# MK64_Power_ADC.net
KiCad netlist of a schematic drawn in Altium Designer
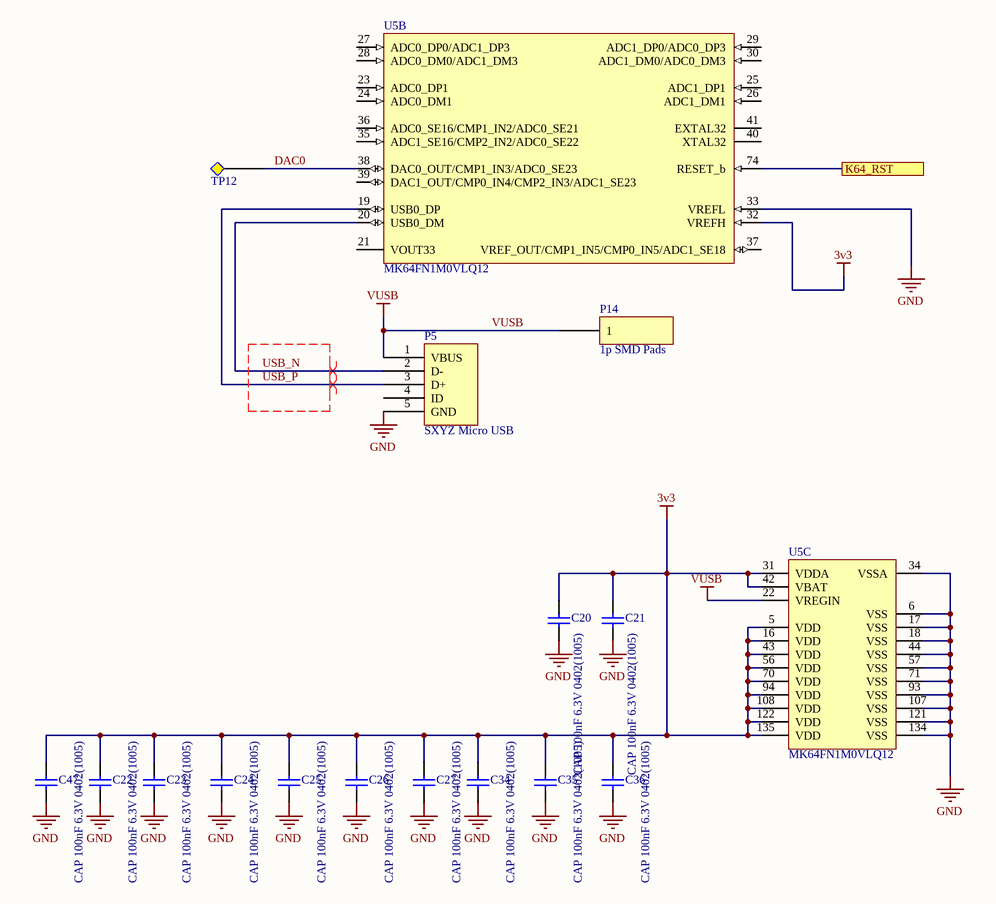
[diagram p0: MK64 Power ADC.SchDoc]

(export (version "E")
  (design (tool "Eeschema 10.0.6"))
  (components
    (comp (ref "C20")
      (value "CAP 100nF 6.3V 0402(1005)")
      (footprint "CAPC0402(1005)60_M")
      (description "CAP 100nF 6.3V ±20% 0402 (1005 Metric) Thickness 0.6mm SMD")
      (fields (field (name "TOLERANCE") "Â±20%"))
      (libsource (lib "Altium Content Vault") (part "CAP"))
    )
    (comp (ref "C21")
      (value "CAP 100nF 6.3V 0402(1005)")
      (footprint "CAPC0402(1005)60_M")
      (description "CAP 100nF 6.3V ±20% 0402 (1005 Metric) Thickness 0.6mm SMD")
      (fields (field (name "TOLERANCE") "Â±20%"))
      (libsource (lib "Altium Content Vault") (part "CAP"))
    )
    (comp (ref "C22")
      (value "CAP 100nF 6.3V 0402(1005)")
      (footprint "CAPC0402(1005)60_M")
      (description "CAP 100nF 6.3V ±20% 0402 (1005 Metric) Thickness 0.6mm SMD")
      (fields (field (name "TOLERANCE") "Â±20%"))
      (libsource (lib "Altium Content Vault") (part "CAP"))
    )
    (comp (ref "C23")
      (value "CAP 100nF 6.3V 0402(1005)")
      (footprint "CAPC0402(1005)60_M")
      (description "CAP 100nF 6.3V ±20% 0402 (1005 Metric) Thickness 0.6mm SMD")
      (fields (field (name "TOLERANCE") "Â±20%"))
      (libsource (lib "Altium Content Vault") (part "CAP"))
    )
    (comp (ref "C24")
      (value "CAP 100nF 6.3V 0402(1005)")
      (footprint "CAPC0402(1005)60_M")
      (description "CAP 100nF 6.3V ±20% 0402 (1005 Metric) Thickness 0.6mm SMD")
      (fields (field (name "TOLERANCE") "Â±20%"))
      (libsource (lib "Altium Content Vault") (part "CAP"))
    )
    (comp (ref "C25")
      (value "CAP 100nF 6.3V 0402(1005)")
      (footprint "CAPC0402(1005)60_M")
      (description "CAP 100nF 6.3V ±20% 0402 (1005 Metric) Thickness 0.6mm SMD")
      (fields (field (name "TOLERANCE") "Â±20%"))
      (libsource (lib "Altium Content Vault") (part "CAP"))
    )
    (comp (ref "C26")
      (value "CAP 100nF 6.3V 0402(1005)")
      (footprint "CAPC0402(1005)60_M")
      (description "CAP 100nF 6.3V ±20% 0402 (1005 Metric) Thickness 0.6mm SMD")
      (fields (field (name "TOLERANCE") "Â±20%"))
      (libsource (lib "Altium Content Vault") (part "CAP"))
    )
    (comp (ref "C27")
      (value "CAP 100nF 6.3V 0402(1005)")
      (footprint "CAPC0402(1005)60_M")
      (description "CAP 100nF 6.3V ±20% 0402 (1005 Metric) Thickness 0.6mm SMD")
      (fields (field (name "TOLERANCE") "Â±20%"))
      (libsource (lib "Altium Content Vault") (part "CAP"))
    )
    (comp (ref "C34")
      (value "CAP 100nF 6.3V 0402(1005)")
      (footprint "CAPC0402(1005)60_M")
      (description "CAP 100nF 6.3V ±20% 0402 (1005 Metric) Thickness 0.6mm SMD")
      (fields (field (name "TOLERANCE") "Â±20%"))
      (libsource (lib "Altium Content Vault") (part "CAP"))
    )
    (comp (ref "C35")
      (value "CAP 100nF 6.3V 0402(1005)")
      (footprint "CAPC0402(1005)60_M")
      (description "CAP 100nF 6.3V ±20% 0402 (1005 Metric) Thickness 0.6mm SMD")
      (fields (field (name "TOLERANCE") "Â±20%"))
      (libsource (lib "Altium Content Vault") (part "CAP"))
    )
    (comp (ref "C36")
      (value "CAP 100nF 6.3V 0402(1005)")
      (footprint "CAPC0402(1005)60_M")
      (description "CAP 100nF 6.3V ±20% 0402 (1005 Metric) Thickness 0.6mm SMD")
      (fields (field (name "TOLERANCE") "Â±20%"))
      (libsource (lib "Altium Content Vault") (part "CAP"))
    )
    (comp (ref "C47")
      (value "CAP 100nF 6.3V 0402(1005)")
      (footprint "CAPC0402(1005)60_M")
      (description "CAP 100nF 6.3V ±20% 0402 (1005 Metric) Thickness 0.6mm SMD")
      (fields (field (name "TOLERANCE") "Â±20%"))
      (libsource (lib "Altium Content Vault") (part "CAP"))
    )
    (comp (ref "P5")
      (value "SXYZ Micro USB")
      (footprint "SXYZ Micro USB")
      (description "Micro USB Connector")
      (libsource (lib "parts") (part "SXYZ MicroUSB"))
    )
    (comp (ref "P14")
      (value "1p SMD Pads")
      (footprint "1p SMD pad")
      (libsource (lib "parts") (part "1p SMD"))
    )
    (comp (ref "TP12") (value "Test Point") (footprint "TP") (libsource (lib "parts") (part "TP")))
    (comp (ref "U5")
      (value "MK64FN1M0VLQ12")
      (footprint "918-03_N")
      (fields (field (name "MANUFACTURER") "Freescale Semiconductor"))
      (libsource (lib "Altium Content Vault") (part "FRES-MK64FX512VLQ12-144"))
    )
  )
  (nets
    (net (code "1") (name "/DAC0") (class "Default")
      (node (ref "TP12") (pin "1") (pinfunction "1_1") (pintype "passive"))
      (node (ref "U5") (pin "38") (pinfunction "DAC0_OUT/CMP1_IN3/ADC0_SE23_38") (pintype "bidirectional"))
    )
    (net (code "2") (name "/K64_RST") (class "Default")
      (node (ref "U5") (pin "74") (pinfunction "RESET_b_74") (pintype "input"))
    )
    (net (code "3") (name "/USB_N") (class "Default")
      (node (ref "P5") (pin "2") (pinfunction "D-_2") (pintype "passive"))
      (node (ref "U5") (pin "20") (pinfunction "USB0_DM_20") (pintype "bidirectional"))
    )
    (net (code "4") (name "/USB_P") (class "Default")
      (node (ref "P5") (pin "3") (pinfunction "D+_3") (pintype "passive"))
      (node (ref "U5") (pin "19") (pinfunction "USB0_DP_19") (pintype "bidirectional"))
    )
    (net (code "5") (name "3v3") (class "Default")
      (node (ref "C20") (pin "2") (pinfunction "2_2") (pintype "passive"))
      (node (ref "C21") (pin "2") (pinfunction "2_2") (pintype "passive"))
      (node (ref "C22") (pin "2") (pinfunction "2_2") (pintype "passive"))
      (node (ref "C23") (pin "2") (pinfunction "2_2") (pintype "passive"))
      (node (ref "C24") (pin "2") (pinfunction "2_2") (pintype "passive"))
      (node (ref "C25") (pin "2") (pinfunction "2_2") (pintype "passive"))
      (node (ref "C26") (pin "2") (pinfunction "2_2") (pintype "passive"))
      (node (ref "C27") (pin "2") (pinfunction "2_2") (pintype "passive"))
      (node (ref "C34") (pin "2") (pinfunction "2_2") (pintype "passive"))
      (node (ref "C35") (pin "2") (pinfunction "2_2") (pintype "passive"))
      (node (ref "C36") (pin "2") (pinfunction "2_2") (pintype "passive"))
      (node (ref "C47") (pin "2") (pinfunction "2_2") (pintype "passive"))
      (node (ref "U5") (pin "108") (pinfunction "VDD_108") (pintype "power_in"))
      (node (ref "U5") (pin "122") (pinfunction "VDD_122") (pintype "power_in"))
      (node (ref "U5") (pin "135") (pinfunction "VDD_135") (pintype "power_in"))
      (node (ref "U5") (pin "16") (pinfunction "VDD_16") (pintype "power_in"))
      (node (ref "U5") (pin "31") (pinfunction "VDDA_31") (pintype "power_in"))
      (node (ref "U5") (pin "32") (pinfunction "VREFH_32") (pintype "input"))
      (node (ref "U5") (pin "42") (pinfunction "VBAT_42") (pintype "power_in"))
      (node (ref "U5") (pin "43") (pinfunction "VDD_43") (pintype "power_in"))
      (node (ref "U5") (pin "5") (pinfunction "VDD_5") (pintype "power_in"))
      (node (ref "U5") (pin "56") (pinfunction "VDD_56") (pintype "power_in"))
      (node (ref "U5") (pin "70") (pinfunction "VDD_70") (pintype "power_in"))
      (node (ref "U5") (pin "94") (pinfunction "VDD_94") (pintype "power_in"))
    )
    (net (code "6") (name "GND") (class "Default")
      (node (ref "C20") (pin "1") (pinfunction "1_1") (pintype "passive"))
      (node (ref "C21") (pin "1") (pinfunction "1_1") (pintype "passive"))
      (node (ref "C22") (pin "1") (pinfunction "1_1") (pintype "passive"))
      (node (ref "C23") (pin "1") (pinfunction "1_1") (pintype "passive"))
      (node (ref "C24") (pin "1") (pinfunction "1_1") (pintype "passive"))
      (node (ref "C25") (pin "1") (pinfunction "1_1") (pintype "passive"))
      (node (ref "C26") (pin "1") (pinfunction "1_1") (pintype "passive"))
      (node (ref "C27") (pin "1") (pinfunction "1_1") (pintype "passive"))
      (node (ref "C34") (pin "1") (pinfunction "1_1") (pintype "passive"))
      (node (ref "C35") (pin "1") (pinfunction "1_1") (pintype "passive"))
      (node (ref "C36") (pin "1") (pinfunction "1_1") (pintype "passive"))
      (node (ref "C47") (pin "1") (pinfunction "1_1") (pintype "passive"))
      (node (ref "P5") (pin "5") (pinfunction "GND_5") (pintype "passive"))
      (node (ref "U5") (pin "107") (pinfunction "VSS_107") (pintype "power_in"))
      (node (ref "U5") (pin "121") (pinfunction "VSS_121") (pintype "power_in"))
      (node (ref "U5") (pin "134") (pinfunction "VSS_134") (pintype "power_in"))
      (node (ref "U5") (pin "17") (pinfunction "VSS_17") (pintype "power_in"))
      (node (ref "U5") (pin "18") (pinfunction "VSS_18") (pintype "power_in"))
      (node (ref "U5") (pin "33") (pinfunction "VREFL_33") (pintype "input"))
      (node (ref "U5") (pin "34") (pinfunction "VSSA_34") (pintype "power_in"))
      (node (ref "U5") (pin "44") (pinfunction "VSS_44") (pintype "power_in"))
      (node (ref "U5") (pin "57") (pinfunction "VSS_57") (pintype "power_in"))
      (node (ref "U5") (pin "6") (pinfunction "VSS_6") (pintype "power_in"))
      (node (ref "U5") (pin "71") (pinfunction "VSS_71") (pintype "power_in"))
      (node (ref "U5") (pin "93") (pinfunction "VSS_93") (pintype "power_in"))
    )
    (net (code "7") (name "VUSB") (class "Default")
      (node (ref "P14") (pin "1") (pinfunction "1_1") (pintype "passive"))
      (node (ref "P5") (pin "1") (pinfunction "VBUS_1") (pintype "passive"))
      (node (ref "U5") (pin "22") (pinfunction "VREGIN_22") (pintype "power_in"))
    )
    (net (code "8") (name "unconnected-(P5-ID-Pad4)") (class "Default")
      (node (ref "P5") (pin "4") (pinfunction "ID_4") (pintype "passive"))
    )
    (net (code "9") (name "unconnected-(U5B-ADC0_DM0{slash}ADC1_DM3-Pad28)") (class "Default")
      (node (ref "U5") (pin "28") (pinfunction "ADC0_DM0/ADC1_DM3_28") (pintype "input"))
    )
    (net (code "10") (name "unconnected-(U5B-ADC0_DM1-Pad24)") (class "Default")
      (node (ref "U5") (pin "24") (pinfunction "ADC0_DM1_24") (pintype "input"))
    )
    (net (code "11") (name "unconnected-(U5B-ADC0_DP0{slash}ADC1_DP3-Pad27)") (class "Default")
      (node (ref "U5") (pin "27") (pinfunction "ADC0_DP0/ADC1_DP3_27") (pintype "input"))
    )
    (net (code "12") (name "unconnected-(U5B-ADC0_DP1-Pad23)") (class "Default")
      (node (ref "U5") (pin "23") (pinfunction "ADC0_DP1_23") (pintype "input"))
    )
    (net (code "13") (name "unconnected-(U5B-ADC0_SE16{slash}CMP1_IN2{slash}ADC0_SE21-Pad36)") (class "Default")
      (node (ref "U5") (pin "36") (pinfunction "ADC0_SE16/CMP1_IN2/ADC0_SE21_36") (pintype "input"))
    )
    (net (code "14") (name "unconnected-(U5B-ADC1_DM0{slash}ADC0_DM3-Pad30)") (class "Default")
      (node (ref "U5") (pin "30") (pinfunction "ADC1_DM0/ADC0_DM3_30") (pintype "input"))
    )
    (net (code "15") (name "unconnected-(U5B-ADC1_DM1-Pad26)") (class "Default")
      (node (ref "U5") (pin "26") (pinfunction "ADC1_DM1_26") (pintype "input"))
    )
    (net (code "16") (name "unconnected-(U5B-ADC1_DP0{slash}ADC0_DP3-Pad29)") (class "Default")
      (node (ref "U5") (pin "29") (pinfunction "ADC1_DP0/ADC0_DP3_29") (pintype "input"))
    )
    (net (code "17") (name "unconnected-(U5B-ADC1_DP1-Pad25)") (class "Default")
      (node (ref "U5") (pin "25") (pinfunction "ADC1_DP1_25") (pintype "input"))
    )
    (net (code "18") (name "unconnected-(U5B-ADC1_SE16{slash}CMP2_IN2{slash}ADC0_SE22-Pad35)") (class "Default")
      (node (ref "U5") (pin "35") (pinfunction "ADC1_SE16/CMP2_IN2/ADC0_SE22_35") (pintype "input"))
    )
    (net (code "19") (name "unconnected-(U5B-DAC1_OUT{slash}CMP0_IN4{slash}CMP2_IN3{slash}ADC1_SE23-Pad39)") (class "Default")
      (node (ref "U5") (pin "39") (pinfunction "DAC1_OUT/CMP0_IN4/CMP2_IN3/ADC1_SE23_39") (pintype "bidirectional"))
    )
    (net (code "20") (name "unconnected-(U5B-EXTAL32-Pad41)") (class "Default")
      (node (ref "U5") (pin "41") (pinfunction "EXTAL32_41") (pintype "passive"))
    )
    (net (code "21") (name "unconnected-(U5B-VOUT33-Pad21)") (class "Default")
      (node (ref "U5") (pin "21") (pinfunction "VOUT33_21") (pintype "power_in"))
    )
    (net (code "22") (name "unconnected-(U5B-VREF_OUT{slash}CMP1_IN5{slash}CMP0_IN5{slash}ADC1_SE18-Pad37)") (class "Default")
      (node (ref "U5") (pin "37") (pinfunction "VREF_OUT/CMP1_IN5/CMP0_IN5/ADC1_SE18_37") (pintype "bidirectional"))
    )
    (net (code "23") (name "unconnected-(U5B-XTAL32-Pad40)") (class "Default")
      (node (ref "U5") (pin "40") (pinfunction "XTAL32_40") (pintype "passive"))
    )
  )
)
